# Switched-3-Output.net
KiCad netlist of a schematic drawn in EAGLE
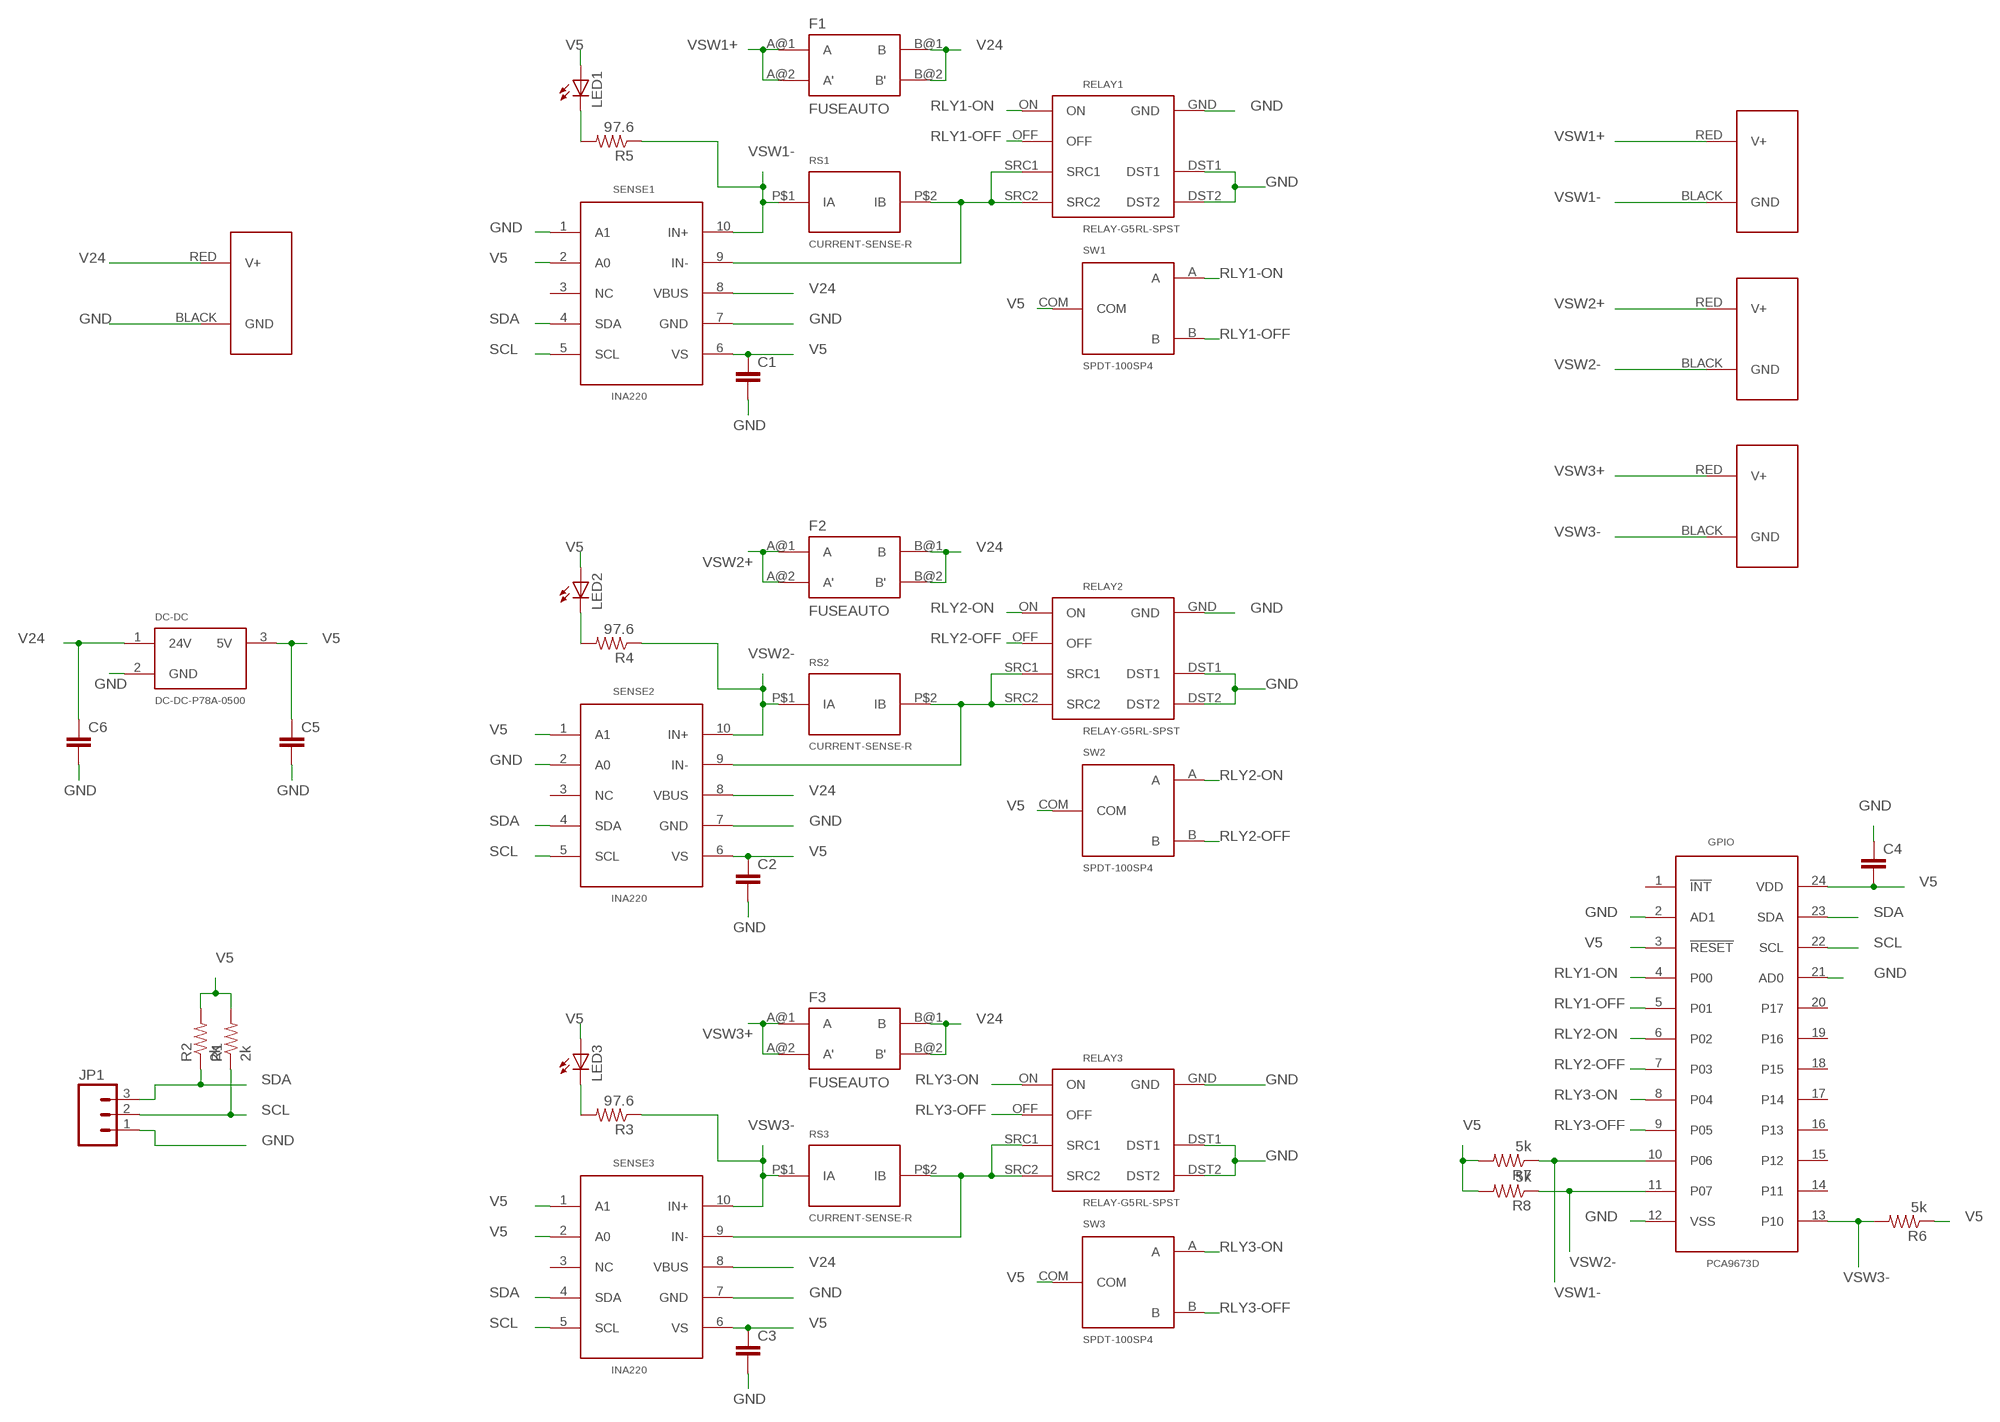
[diagram p0: schematic, sheet 1]

(export (version "E")
  (design (tool "Eeschema 10.0.6"))
  (components
    (comp (ref "C1")
      (value "C-EUC0805")
      (footprint "eagle-import:C0805")
      (libsource (lib "eagle-import") (part "C-EUC0805"))
    )
    (comp (ref "C2")
      (value "C-EUC0805")
      (footprint "eagle-import:C0805")
      (libsource (lib "eagle-import") (part "C-EUC0805"))
    )
    (comp (ref "C3")
      (value "C-EUC0805")
      (footprint "eagle-import:C0805")
      (libsource (lib "eagle-import") (part "C-EUC0805"))
    )
    (comp (ref "C4")
      (value "C-EUC0805")
      (footprint "eagle-import:C0805")
      (libsource (lib "eagle-import") (part "C-EUC0805"))
    )
    (comp (ref "C5")
      (value "C-EUC0805")
      (footprint "eagle-import:C0805")
      (libsource (lib "eagle-import") (part "C-EUC0805"))
    )
    (comp (ref "C6")
      (value "C-EUC0805")
      (footprint "eagle-import:C0805")
      (libsource (lib "eagle-import") (part "C-EUC0805"))
    )
    (comp (ref "DC-DC")
      (value "DC-DC-P78A-0500")
      (footprint "eagle-import:DC-DC-P78A-0500")
      (libsource (lib "eagle-import") (part "DC-DC-P78A-0500"))
    )
    (comp (ref "F1")
      (value "FUSEAUTO")
      (footprint "eagle-import:FUSE")
      (libsource (lib "eagle-import") (part "FUSEAUTO"))
    )
    (comp (ref "F2")
      (value "FUSEAUTO")
      (footprint "eagle-import:FUSE")
      (libsource (lib "eagle-import") (part "FUSEAUTO"))
    )
    (comp (ref "F3")
      (value "FUSEAUTO")
      (footprint "eagle-import:FUSE")
      (libsource (lib "eagle-import") (part "FUSEAUTO"))
    )
    (comp (ref "GPIO")
      (value "PCA9673D")
      (footprint "eagle-import:SO24")
      (libsource (lib "eagle-import") (part "PCA9673D"))
    )
    (comp (ref "JP1")
      (value "M03PTH")
      (footprint "eagle-import:1X03")
      (libsource (lib "eagle-import") (part "M03PTH"))
    )
    (comp (ref "LED1")
      (value "LED3MM")
      (footprint "eagle-import:LED3MM")
      (libsource (lib "eagle-import") (part "LED3MM"))
    )
    (comp (ref "LED2")
      (value "LED3MM")
      (footprint "eagle-import:LED3MM")
      (libsource (lib "eagle-import") (part "LED3MM"))
    )
    (comp (ref "LED3")
      (value "LED3MM")
      (footprint "eagle-import:LED3MM")
      (libsource (lib "eagle-import") (part "LED3MM"))
    )
    (comp (ref "PWR")
      (value "POWERPOLE_POWER45A_DRILL")
      (footprint "eagle-import:POWERPOLE_PAIR_45A_HOLE")
      (libsource (lib "eagle-import") (part "POWERPOLE_POWER45A_DRILL"))
    )
    (comp (ref "R1")
      (value "2k")
      (footprint "eagle-import:R0805")
      (libsource (lib "eagle-import") (part "R-US_R0805"))
    )
    (comp (ref "R2")
      (value "2k")
      (footprint "eagle-import:R0805")
      (libsource (lib "eagle-import") (part "R-US_R0805"))
    )
    (comp (ref "R3")
      (value "97.6")
      (footprint "eagle-import:R0805")
      (libsource (lib "eagle-import") (part "R-US_R0805"))
    )
    (comp (ref "R4")
      (value "97.6")
      (footprint "eagle-import:R0805")
      (libsource (lib "eagle-import") (part "R-US_R0805"))
    )
    (comp (ref "R5")
      (value "97.6")
      (footprint "eagle-import:R0805")
      (libsource (lib "eagle-import") (part "R-US_R0805"))
    )
    (comp (ref "R6")
      (value "5k")
      (footprint "eagle-import:R0805")
      (libsource (lib "eagle-import") (part "R-US_R0805"))
    )
    (comp (ref "R7")
      (value "5k")
      (footprint "eagle-import:R0805")
      (libsource (lib "eagle-import") (part "R-US_R0805"))
    )
    (comp (ref "R8")
      (value "5k")
      (footprint "eagle-import:R0805")
      (libsource (lib "eagle-import") (part "R-US_R0805"))
    )
    (comp (ref "RELAY1")
      (value "RELAY-G5RL-SPST")
      (footprint "eagle-import:RELAY-G5RL-SPST")
      (libsource (lib "eagle-import") (part "RELAY-G5RL-SPST"))
    )
    (comp (ref "RELAY2")
      (value "RELAY-G5RL-SPST")
      (footprint "eagle-import:RELAY-G5RL-SPST")
      (libsource (lib "eagle-import") (part "RELAY-G5RL-SPST"))
    )
    (comp (ref "RELAY3")
      (value "RELAY-G5RL-SPST")
      (footprint "eagle-import:RELAY-G5RL-SPST")
      (libsource (lib "eagle-import") (part "RELAY-G5RL-SPST"))
    )
    (comp (ref "RS1")
      (value "CURRENT-SENSE-R")
      (footprint "eagle-import:CURRENT-SENSE-R")
      (libsource (lib "eagle-import") (part "CURRENT-SENSE-R"))
    )
    (comp (ref "RS2")
      (value "CURRENT-SENSE-R")
      (footprint "eagle-import:CURRENT-SENSE-R")
      (libsource (lib "eagle-import") (part "CURRENT-SENSE-R"))
    )
    (comp (ref "RS3")
      (value "CURRENT-SENSE-R")
      (footprint "eagle-import:CURRENT-SENSE-R")
      (libsource (lib "eagle-import") (part "CURRENT-SENSE-R"))
    )
    (comp (ref "SENSE1")
      (value "INA220")
      (footprint "eagle-import:SOP-10")
      (libsource (lib "eagle-import") (part "INA220"))
    )
    (comp (ref "SENSE2")
      (value "INA220")
      (footprint "eagle-import:SOP-10")
      (libsource (lib "eagle-import") (part "INA220"))
    )
    (comp (ref "SENSE3")
      (value "INA220")
      (footprint "eagle-import:SOP-10")
      (libsource (lib "eagle-import") (part "INA220"))
    )
    (comp (ref "SW1")
      (value "SPDT-100SP4")
      (footprint "eagle-import:SPDT-100SP4")
      (libsource (lib "eagle-import") (part "SPDT-100SP4"))
    )
    (comp (ref "SW2")
      (value "SPDT-100SP4")
      (footprint "eagle-import:SPDT-100SP4")
      (libsource (lib "eagle-import") (part "SPDT-100SP4"))
    )
    (comp (ref "SW3")
      (value "SPDT-100SP4")
      (footprint "eagle-import:SPDT-100SP4")
      (libsource (lib "eagle-import") (part "SPDT-100SP4"))
    )
    (comp (ref "VSW1")
      (value "POWERPOLE_POWER45A_DRILL")
      (footprint "eagle-import:POWERPOLE_PAIR_45A_HOLE")
      (libsource (lib "eagle-import") (part "POWERPOLE_POWER45A_DRILL"))
    )
    (comp (ref "VSW2")
      (value "POWERPOLE_POWER45A_DRILL")
      (footprint "eagle-import:POWERPOLE_PAIR_45A_HOLE")
      (libsource (lib "eagle-import") (part "POWERPOLE_POWER45A_DRILL"))
    )
    (comp (ref "VSW3")
      (value "POWERPOLE_POWER45A_DRILL")
      (footprint "eagle-import:POWERPOLE_PAIR_45A_HOLE")
      (libsource (lib "eagle-import") (part "POWERPOLE_POWER45A_DRILL"))
    )
  )
  (nets
    (net (code "1") (name "/GND") (class "Default")
      (node (ref "C1") (pin "2") (pinfunction "2_2") (pintype "passive"))
      (node (ref "C2") (pin "2") (pinfunction "2_2") (pintype "passive"))
      (node (ref "C3") (pin "2") (pinfunction "2_2") (pintype "passive"))
      (node (ref "C4") (pin "1") (pinfunction "1_1") (pintype "passive"))
      (node (ref "C5") (pin "2") (pinfunction "2_2") (pintype "passive"))
      (node (ref "C6") (pin "2") (pinfunction "2_2") (pintype "passive"))
      (node (ref "DC-DC") (pin "2") (pinfunction "GND_2") (pintype "power_in"))
      (node (ref "GPIO") (pin "12") (pinfunction "VSS_12") (pintype "bidirectional"))
      (node (ref "GPIO") (pin "2") (pinfunction "AD1_2") (pintype "bidirectional"))
      (node (ref "GPIO") (pin "21") (pinfunction "AD0_21") (pintype "bidirectional"))
      (node (ref "JP1") (pin "1") (pinfunction "1_1") (pintype "passive"))
      (node (ref "PWR") (pin "BLACK") (pinfunction "GND_BLACK") (pintype "power_in"))
      (node (ref "RELAY1") (pin "DST1") (pinfunction "DST1_DST1") (pintype "output"))
      (node (ref "RELAY1") (pin "DST2") (pinfunction "DST2_DST2") (pintype "output"))
      (node (ref "RELAY1") (pin "GND") (pinfunction "GND_GND") (pintype "power_in"))
      (node (ref "RELAY2") (pin "DST1") (pinfunction "DST1_DST1") (pintype "output"))
      (node (ref "RELAY2") (pin "DST2") (pinfunction "DST2_DST2") (pintype "output"))
      (node (ref "RELAY2") (pin "GND") (pinfunction "GND_GND") (pintype "power_in"))
      (node (ref "RELAY3") (pin "DST1") (pinfunction "DST1_DST1") (pintype "output"))
      (node (ref "RELAY3") (pin "DST2") (pinfunction "DST2_DST2") (pintype "output"))
      (node (ref "RELAY3") (pin "GND") (pinfunction "GND_GND") (pintype "power_in"))
      (node (ref "SENSE1") (pin "1") (pinfunction "A1_1") (pintype "input"))
      (node (ref "SENSE1") (pin "7") (pinfunction "GND_7") (pintype "power_in"))
      (node (ref "SENSE2") (pin "2") (pinfunction "A0_2") (pintype "input"))
      (node (ref "SENSE2") (pin "7") (pinfunction "GND_7") (pintype "power_in"))
      (node (ref "SENSE3") (pin "7") (pinfunction "GND_7") (pintype "power_in"))
    )
    (net (code "2") (name "/RLY1-OFF") (class "Default")
      (node (ref "GPIO") (pin "5") (pinfunction "P01_5") (pintype "bidirectional"))
      (node (ref "RELAY1") (pin "OFF") (pinfunction "OFF_OFF") (pintype "input"))
      (node (ref "SW1") (pin "B") (pinfunction "B_B") (pintype "output"))
    )
    (net (code "3") (name "/RLY1-ON") (class "Default")
      (node (ref "GPIO") (pin "4") (pinfunction "P00_4") (pintype "bidirectional"))
      (node (ref "RELAY1") (pin "ON") (pinfunction "ON_ON") (pintype "input"))
      (node (ref "SW1") (pin "A") (pinfunction "A_A") (pintype "output"))
    )
    (net (code "4") (name "/RLY2-OFF") (class "Default")
      (node (ref "GPIO") (pin "7") (pinfunction "P03_7") (pintype "bidirectional"))
      (node (ref "RELAY2") (pin "OFF") (pinfunction "OFF_OFF") (pintype "input"))
      (node (ref "SW2") (pin "B") (pinfunction "B_B") (pintype "output"))
    )
    (net (code "5") (name "/RLY2-ON") (class "Default")
      (node (ref "GPIO") (pin "6") (pinfunction "P02_6") (pintype "bidirectional"))
      (node (ref "RELAY2") (pin "ON") (pinfunction "ON_ON") (pintype "input"))
      (node (ref "SW2") (pin "A") (pinfunction "A_A") (pintype "output"))
    )
    (net (code "6") (name "/RLY3-OFF") (class "Default")
      (node (ref "GPIO") (pin "9") (pinfunction "P05_9") (pintype "bidirectional"))
      (node (ref "RELAY3") (pin "OFF") (pinfunction "OFF_OFF") (pintype "input"))
      (node (ref "SW3") (pin "B") (pinfunction "B_B") (pintype "output"))
    )
    (net (code "7") (name "/RLY3-ON") (class "Default")
      (node (ref "GPIO") (pin "8") (pinfunction "P04_8") (pintype "bidirectional"))
      (node (ref "RELAY3") (pin "ON") (pinfunction "ON_ON") (pintype "input"))
      (node (ref "SW3") (pin "A") (pinfunction "A_A") (pintype "output"))
    )
    (net (code "8") (name "/SCL") (class "Default")
      (node (ref "GPIO") (pin "22") (pinfunction "SCL_22") (pintype "bidirectional"))
      (node (ref "JP1") (pin "2") (pinfunction "2_2") (pintype "passive"))
      (node (ref "R1") (pin "1") (pinfunction "1_1") (pintype "passive"))
      (node (ref "SENSE1") (pin "5") (pinfunction "SCL_5") (pintype "bidirectional"))
      (node (ref "SENSE2") (pin "5") (pinfunction "SCL_5") (pintype "bidirectional"))
      (node (ref "SENSE3") (pin "5") (pinfunction "SCL_5") (pintype "bidirectional"))
    )
    (net (code "9") (name "/SDA") (class "Default")
      (node (ref "GPIO") (pin "23") (pinfunction "SDA_23") (pintype "bidirectional"))
      (node (ref "JP1") (pin "3") (pinfunction "3_3") (pintype "passive"))
      (node (ref "R2") (pin "1") (pinfunction "1_1") (pintype "passive"))
      (node (ref "SENSE1") (pin "4") (pinfunction "SDA_4") (pintype "bidirectional"))
      (node (ref "SENSE2") (pin "4") (pinfunction "SDA_4") (pintype "bidirectional"))
      (node (ref "SENSE3") (pin "4") (pinfunction "SDA_4") (pintype "bidirectional"))
    )
    (net (code "10") (name "/V5") (class "Default")
      (node (ref "C1") (pin "1") (pinfunction "1_1") (pintype "passive"))
      (node (ref "C2") (pin "1") (pinfunction "1_1") (pintype "passive"))
      (node (ref "C3") (pin "1") (pinfunction "1_1") (pintype "passive"))
      (node (ref "C4") (pin "2") (pinfunction "2_2") (pintype "passive"))
      (node (ref "C5") (pin "1") (pinfunction "1_1") (pintype "passive"))
      (node (ref "DC-DC") (pin "3") (pinfunction "5V_3") (pintype "power_in"))
      (node (ref "GPIO") (pin "24") (pinfunction "VDD_24") (pintype "bidirectional"))
      (node (ref "GPIO") (pin "3") (pinfunction "~{RESET}_3") (pintype "bidirectional"))
      (node (ref "LED1") (pin "A") (pinfunction "A_A") (pintype "passive"))
      (node (ref "LED2") (pin "A") (pinfunction "A_A") (pintype "passive"))
      (node (ref "LED3") (pin "A") (pinfunction "A_A") (pintype "passive"))
      (node (ref "R1") (pin "2") (pinfunction "2_2") (pintype "passive"))
      (node (ref "R2") (pin "2") (pinfunction "2_2") (pintype "passive"))
      (node (ref "R6") (pin "1") (pinfunction "1_1") (pintype "passive"))
      (node (ref "R7") (pin "2") (pinfunction "2_2") (pintype "passive"))
      (node (ref "R8") (pin "2") (pinfunction "2_2") (pintype "passive"))
      (node (ref "SENSE1") (pin "2") (pinfunction "A0_2") (pintype "input"))
      (node (ref "SENSE1") (pin "6") (pinfunction "VS_6") (pintype "power_in"))
      (node (ref "SENSE2") (pin "1") (pinfunction "A1_1") (pintype "input"))
      (node (ref "SENSE2") (pin "6") (pinfunction "VS_6") (pintype "power_in"))
      (node (ref "SENSE3") (pin "1") (pinfunction "A1_1") (pintype "input"))
      (node (ref "SENSE3") (pin "2") (pinfunction "A0_2") (pintype "input"))
      (node (ref "SENSE3") (pin "6") (pinfunction "VS_6") (pintype "power_in"))
      (node (ref "SW1") (pin "COM") (pinfunction "COM_COM") (pintype "input"))
      (node (ref "SW2") (pin "COM") (pinfunction "COM_COM") (pintype "input"))
      (node (ref "SW3") (pin "COM") (pinfunction "COM_COM") (pintype "input"))
    )
    (net (code "11") (name "/V24") (class "Default")
      (node (ref "C6") (pin "1") (pinfunction "1_1") (pintype "passive"))
      (node (ref "DC-DC") (pin "1") (pinfunction "24V_1") (pintype "power_in"))
      (node (ref "F1") (pin "B@1") (pinfunction "B_B@1") (pintype "bidirectional"))
      (node (ref "F1") (pin "B@2") (pinfunction "B'_B@2") (pintype "bidirectional"))
      (node (ref "F2") (pin "B@1") (pinfunction "B_B@1") (pintype "bidirectional"))
      (node (ref "F2") (pin "B@2") (pinfunction "B'_B@2") (pintype "bidirectional"))
      (node (ref "F3") (pin "B@1") (pinfunction "B_B@1") (pintype "bidirectional"))
      (node (ref "F3") (pin "B@2") (pinfunction "B'_B@2") (pintype "bidirectional"))
      (node (ref "PWR") (pin "RED") (pinfunction "V+_RED") (pintype "power_in"))
      (node (ref "SENSE1") (pin "8") (pinfunction "VBUS_8") (pintype "power_in"))
      (node (ref "SENSE2") (pin "8") (pinfunction "VBUS_8") (pintype "power_in"))
      (node (ref "SENSE3") (pin "8") (pinfunction "VBUS_8") (pintype "power_in"))
    )
    (net (code "12") (name "/VSW1+") (class "Default")
      (node (ref "F1") (pin "A@1") (pinfunction "A_A@1") (pintype "bidirectional"))
      (node (ref "F1") (pin "A@2") (pinfunction "A'_A@2") (pintype "bidirectional"))
      (node (ref "VSW1") (pin "RED") (pinfunction "V+_RED") (pintype "power_in"))
    )
    (net (code "13") (name "/VSW1-") (class "Default")
      (node (ref "GPIO") (pin "10") (pinfunction "P06_10") (pintype "bidirectional"))
      (node (ref "R5") (pin "1") (pinfunction "1_1") (pintype "passive"))
      (node (ref "R7") (pin "1") (pinfunction "1_1") (pintype "passive"))
      (node (ref "RS1") (pin "P$1") (pinfunction "IA_P$1") (pintype "power_in"))
      (node (ref "SENSE1") (pin "10") (pinfunction "IN+_10") (pintype "input"))
      (node (ref "VSW1") (pin "BLACK") (pinfunction "GND_BLACK") (pintype "power_in"))
    )
    (net (code "14") (name "/VSW2+") (class "Default")
      (node (ref "F2") (pin "A@1") (pinfunction "A_A@1") (pintype "bidirectional"))
      (node (ref "F2") (pin "A@2") (pinfunction "A'_A@2") (pintype "bidirectional"))
      (node (ref "VSW2") (pin "RED") (pinfunction "V+_RED") (pintype "power_in"))
    )
    (net (code "15") (name "/VSW2-") (class "Default")
      (node (ref "GPIO") (pin "11") (pinfunction "P07_11") (pintype "bidirectional"))
      (node (ref "R4") (pin "1") (pinfunction "1_1") (pintype "passive"))
      (node (ref "R8") (pin "1") (pinfunction "1_1") (pintype "passive"))
      (node (ref "RS2") (pin "P$1") (pinfunction "IA_P$1") (pintype "power_in"))
      (node (ref "SENSE2") (pin "10") (pinfunction "IN+_10") (pintype "input"))
      (node (ref "VSW2") (pin "BLACK") (pinfunction "GND_BLACK") (pintype "power_in"))
    )
    (net (code "16") (name "/VSW3+") (class "Default")
      (node (ref "F3") (pin "A@1") (pinfunction "A_A@1") (pintype "bidirectional"))
      (node (ref "F3") (pin "A@2") (pinfunction "A'_A@2") (pintype "bidirectional"))
      (node (ref "VSW3") (pin "RED") (pinfunction "V+_RED") (pintype "power_in"))
    )
    (net (code "17") (name "/VSW3-") (class "Default")
      (node (ref "GPIO") (pin "13") (pinfunction "P10_13") (pintype "bidirectional"))
      (node (ref "R3") (pin "1") (pinfunction "1_1") (pintype "passive"))
      (node (ref "R6") (pin "2") (pinfunction "2_2") (pintype "passive"))
      (node (ref "RS3") (pin "P$1") (pinfunction "IA_P$1") (pintype "power_in"))
      (node (ref "SENSE3") (pin "10") (pinfunction "IN+_10") (pintype "input"))
      (node (ref "VSW3") (pin "BLACK") (pinfunction "GND_BLACK") (pintype "power_in"))
    )
    (net (code "18") (name "Net-(LED1-C)") (class "Default")
      (node (ref "LED1") (pin "K") (pinfunction "C_K") (pintype "passive"))
      (node (ref "R5") (pin "2") (pinfunction "2_2") (pintype "passive"))
    )
    (net (code "19") (name "Net-(LED2-C)") (class "Default")
      (node (ref "LED2") (pin "K") (pinfunction "C_K") (pintype "passive"))
      (node (ref "R4") (pin "2") (pinfunction "2_2") (pintype "passive"))
    )
    (net (code "20") (name "Net-(LED3-C)") (class "Default")
      (node (ref "LED3") (pin "K") (pinfunction "C_K") (pintype "passive"))
      (node (ref "R3") (pin "2") (pinfunction "2_2") (pintype "passive"))
    )
    (net (code "21") (name "Net-(RS1-IB)") (class "Default")
      (node (ref "RELAY1") (pin "SRC1") (pinfunction "SRC1_SRC1") (pintype "input"))
      (node (ref "RELAY1") (pin "SRC2") (pinfunction "SRC2_SRC2") (pintype "input"))
      (node (ref "RS1") (pin "P$2") (pinfunction "IB_P$2") (pintype "power_in"))
      (node (ref "SENSE1") (pin "9") (pinfunction "IN-_9") (pintype "input"))
    )
    (net (code "22") (name "Net-(RS2-IB)") (class "Default")
      (node (ref "RELAY2") (pin "SRC1") (pinfunction "SRC1_SRC1") (pintype "input"))
      (node (ref "RELAY2") (pin "SRC2") (pinfunction "SRC2_SRC2") (pintype "input"))
      (node (ref "RS2") (pin "P$2") (pinfunction "IB_P$2") (pintype "power_in"))
      (node (ref "SENSE2") (pin "9") (pinfunction "IN-_9") (pintype "input"))
    )
    (net (code "23") (name "Net-(RS3-IB)") (class "Default")
      (node (ref "RELAY3") (pin "SRC1") (pinfunction "SRC1_SRC1") (pintype "input"))
      (node (ref "RELAY3") (pin "SRC2") (pinfunction "SRC2_SRC2") (pintype "input"))
      (node (ref "RS3") (pin "P$2") (pinfunction "IB_P$2") (pintype "power_in"))
      (node (ref "SENSE3") (pin "9") (pinfunction "IN-_9") (pintype "input"))
    )
    (net (code "24") (name "unconnected-(GPIO-P11-Pad14)") (class "Default")
      (node (ref "GPIO") (pin "14") (pinfunction "P11_14") (pintype "bidirectional"))
    )
    (net (code "25") (name "unconnected-(GPIO-P12-Pad15)") (class "Default")
      (node (ref "GPIO") (pin "15") (pinfunction "P12_15") (pintype "bidirectional"))
    )
    (net (code "26") (name "unconnected-(GPIO-P13-Pad16)") (class "Default")
      (node (ref "GPIO") (pin "16") (pinfunction "P13_16") (pintype "bidirectional"))
    )
    (net (code "27") (name "unconnected-(GPIO-P14-Pad17)") (class "Default")
      (node (ref "GPIO") (pin "17") (pinfunction "P14_17") (pintype "bidirectional"))
    )
    (net (code "28") (name "unconnected-(GPIO-P15-Pad18)") (class "Default")
      (node (ref "GPIO") (pin "18") (pinfunction "P15_18") (pintype "bidirectional"))
    )
    (net (code "29") (name "unconnected-(GPIO-P16-Pad19)") (class "Default")
      (node (ref "GPIO") (pin "19") (pinfunction "P16_19") (pintype "bidirectional"))
    )
    (net (code "30") (name "unconnected-(GPIO-P17-Pad20)") (class "Default")
      (node (ref "GPIO") (pin "20") (pinfunction "P17_20") (pintype "bidirectional"))
    )
    (net (code "31") (name "unconnected-(GPIO-~{INT}-Pad1)") (class "Default")
      (node (ref "GPIO") (pin "1") (pinfunction "~{INT}_1") (pintype "bidirectional"))
    )
    (net (code "32") (name "unconnected-(SENSE1-NC-Pad3)") (class "Default")
      (node (ref "SENSE1") (pin "3") (pinfunction "NC_3") (pintype "no_connect"))
    )
    (net (code "33") (name "unconnected-(SENSE2-NC-Pad3)") (class "Default")
      (node (ref "SENSE2") (pin "3") (pinfunction "NC_3") (pintype "no_connect"))
    )
    (net (code "34") (name "unconnected-(SENSE3-NC-Pad3)") (class "Default")
      (node (ref "SENSE3") (pin "3") (pinfunction "NC_3") (pintype "no_connect"))
    )
  )
)
